# bilancia_smart_no_route.net
KiCad netlist of a schematic drawn in EAGLE
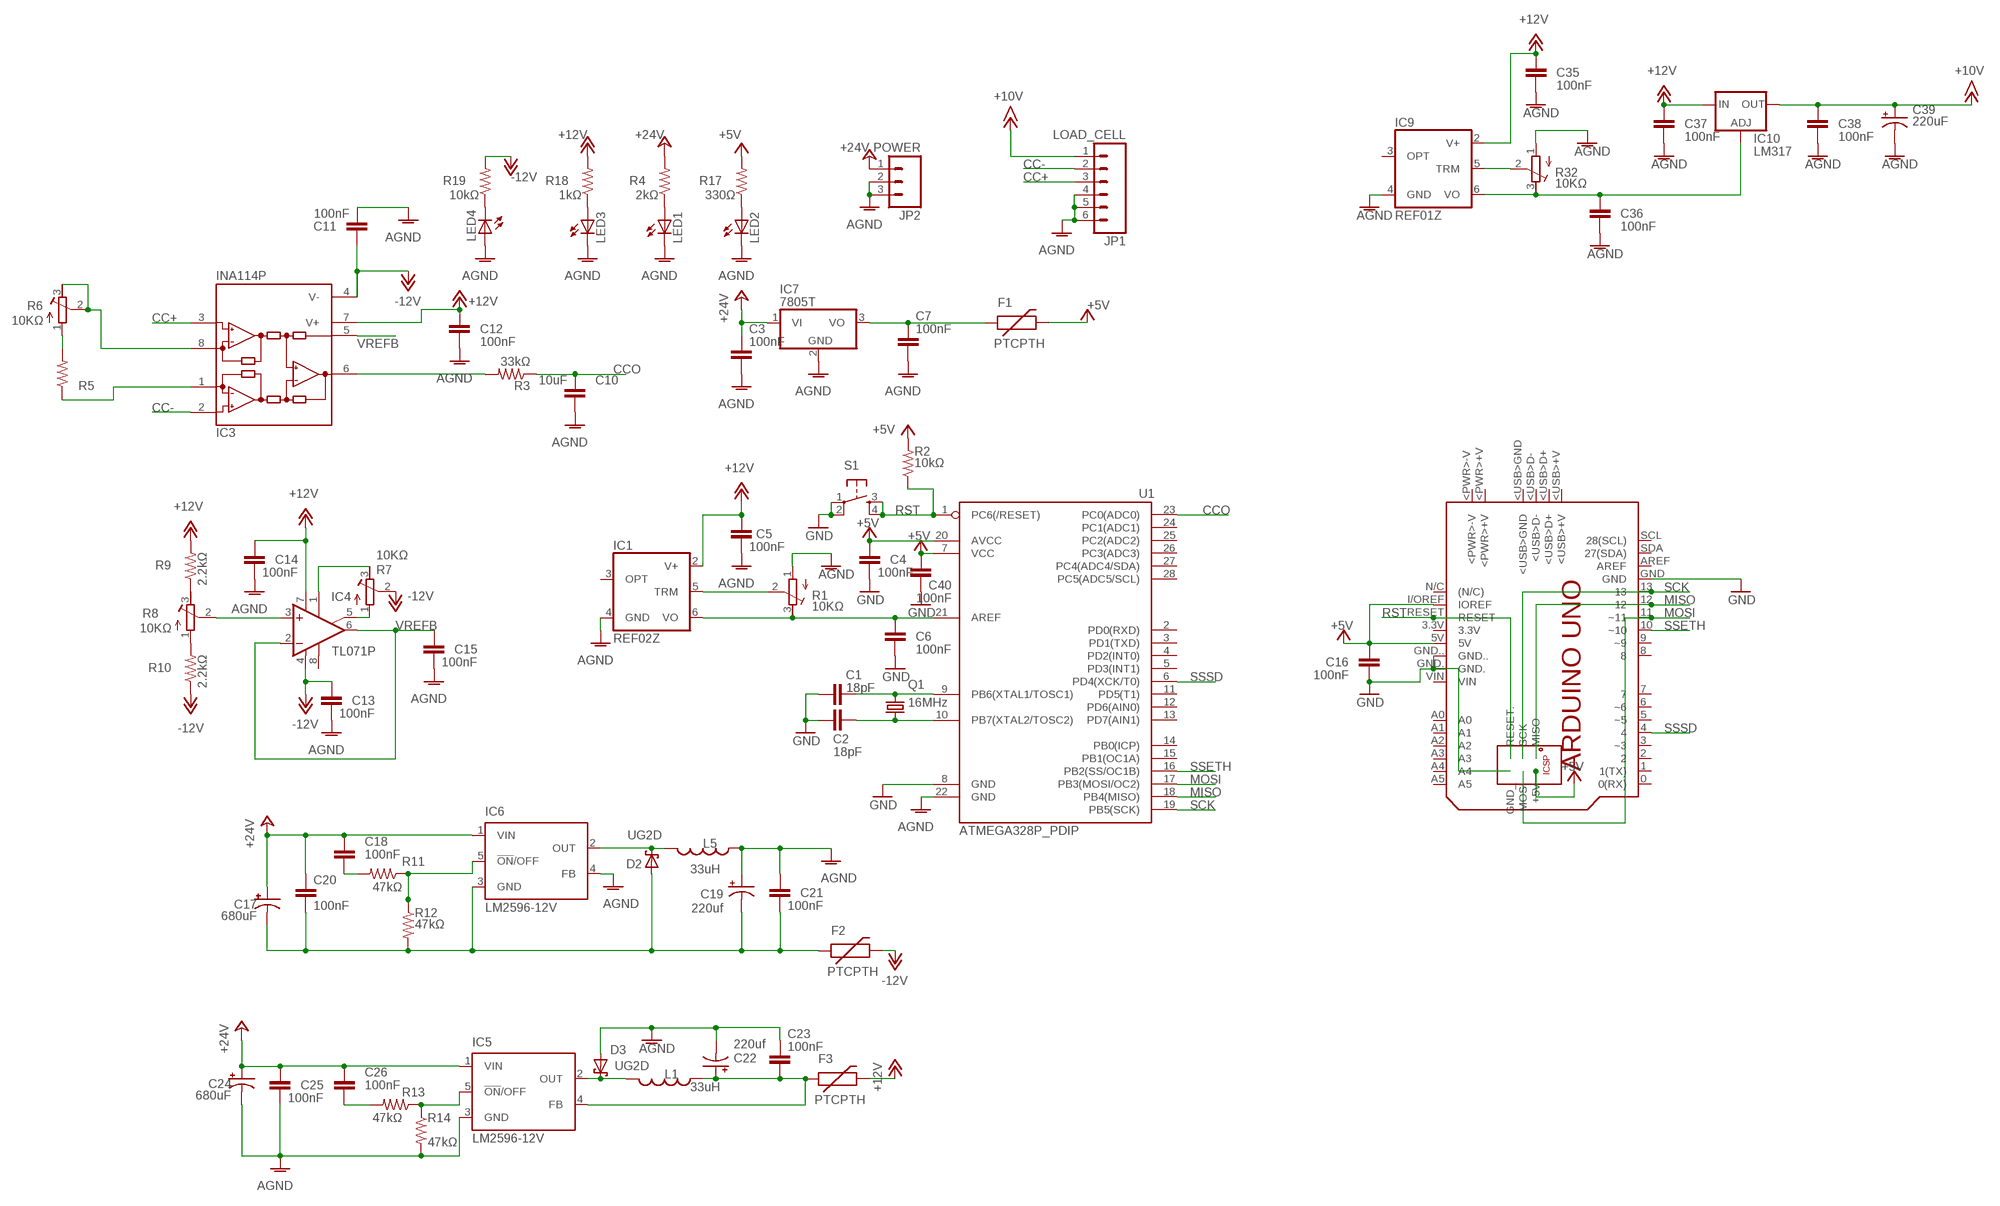
[diagram p0: schematic, sheet 1]

(export (version "E")
  (design (tool "Eeschema 10.0.6"))
  (components
    (comp (ref "C1")
      (value "18pF")
      (footprint "eagle-import:C2.5-2")
      (libsource (lib "eagle-import") (part "C2.5/2"))
    )
    (comp (ref "C2")
      (value "18pF")
      (footprint "eagle-import:C2.5-2")
      (libsource (lib "eagle-import") (part "C2.5/2"))
    )
    (comp (ref "C3")
      (value "100nF")
      (footprint "eagle-import:C2.5-2")
      (libsource (lib "eagle-import") (part "C2.5/2"))
    )
    (comp (ref "C4")
      (value "100nF")
      (footprint "eagle-import:C2.5-2")
      (libsource (lib "eagle-import") (part "C2.5/2"))
    )
    (comp (ref "C5")
      (value "100nF")
      (footprint "eagle-import:C2.5-2")
      (libsource (lib "eagle-import") (part "C2.5/2"))
    )
    (comp (ref "C6")
      (value "100nF")
      (footprint "eagle-import:C2.5-2")
      (libsource (lib "eagle-import") (part "C2.5/2"))
    )
    (comp (ref "C7")
      (value "100nF")
      (footprint "eagle-import:C2.5-2")
      (libsource (lib "eagle-import") (part "C2.5/2"))
    )
    (comp (ref "C10")
      (value "10uF")
      (footprint "eagle-import:C2.5-2")
      (libsource (lib "eagle-import") (part "C2.5/2"))
    )
    (comp (ref "C11")
      (value "100nF")
      (footprint "eagle-import:C2.5-2")
      (libsource (lib "eagle-import") (part "C2.5/2"))
    )
    (comp (ref "C12")
      (value "100nF")
      (footprint "eagle-import:C2.5-2")
      (libsource (lib "eagle-import") (part "C2.5/2"))
    )
    (comp (ref "C13")
      (value "100nF")
      (footprint "eagle-import:C2.5-2")
      (libsource (lib "eagle-import") (part "C2.5/2"))
    )
    (comp (ref "C14")
      (value "100nF")
      (footprint "eagle-import:C2.5-2")
      (libsource (lib "eagle-import") (part "C2.5/2"))
    )
    (comp (ref "C15")
      (value "100nF")
      (footprint "eagle-import:C2.5-2")
      (libsource (lib "eagle-import") (part "C2.5/2"))
    )
    (comp (ref "C16")
      (value "100nF")
      (footprint "eagle-import:C2.5-2")
      (libsource (lib "eagle-import") (part "C2.5/2"))
    )
    (comp (ref "C17")
      (value "680uF")
      (footprint "eagle-import:E5-8,5")
      (libsource (lib "eagle-import") (part "CPOL-USE5-8.5"))
    )
    (comp (ref "C18")
      (value "100nF")
      (footprint "eagle-import:C2.5-2")
      (libsource (lib "eagle-import") (part "C2.5/2"))
    )
    (comp (ref "C19")
      (value "220uf")
      (footprint "eagle-import:E5-8,5")
      (libsource (lib "eagle-import") (part "CPOL-USE5-8.5"))
    )
    (comp (ref "C20")
      (value "100nF")
      (footprint "eagle-import:C2.5-2")
      (libsource (lib "eagle-import") (part "C2.5/2"))
    )
    (comp (ref "C21")
      (value "100nF")
      (footprint "eagle-import:C2.5-2")
      (libsource (lib "eagle-import") (part "C2.5/2"))
    )
    (comp (ref "C22")
      (value "220uf")
      (footprint "eagle-import:E5-8,5")
      (libsource (lib "eagle-import") (part "CPOL-USE5-8.5"))
    )
    (comp (ref "C23")
      (value "100nF")
      (footprint "eagle-import:C2.5-2")
      (libsource (lib "eagle-import") (part "C2.5/2"))
    )
    (comp (ref "C24")
      (value "680uF")
      (footprint "eagle-import:E5-8,5")
      (libsource (lib "eagle-import") (part "CPOL-USE5-8.5"))
    )
    (comp (ref "C25")
      (value "100nF")
      (footprint "eagle-import:C2.5-2")
      (libsource (lib "eagle-import") (part "C2.5/2"))
    )
    (comp (ref "C26")
      (value "100nF")
      (footprint "eagle-import:C2.5-2")
      (libsource (lib "eagle-import") (part "C2.5/2"))
    )
    (comp (ref "C35")
      (value "100nF")
      (footprint "eagle-import:C2.5-2")
      (libsource (lib "eagle-import") (part "C2.5/2"))
    )
    (comp (ref "C36")
      (value "100nF")
      (footprint "eagle-import:C2.5-2")
      (libsource (lib "eagle-import") (part "C2.5/2"))
    )
    (comp (ref "C37")
      (value "100nF")
      (footprint "eagle-import:C2.5-2")
      (libsource (lib "eagle-import") (part "C2.5/2"))
    )
    (comp (ref "C38")
      (value "100nF")
      (footprint "eagle-import:C2.5-2")
      (libsource (lib "eagle-import") (part "C2.5/2"))
    )
    (comp (ref "C39")
      (value "220uF")
      (footprint "eagle-import:CPOL-RADIAL-100UF-25V")
      (libsource (lib "eagle-import") (part "CAP_POLPTH1"))
    )
    (comp (ref "C40")
      (value "100nF")
      (footprint "eagle-import:C2.5-2")
      (libsource (lib "eagle-import") (part "C2.5/2"))
    )
    (comp (ref "D2")
      (value "UG2D")
      (footprint "eagle-import:DO41-7")
      (libsource (lib "eagle-import") (part "SCHOTTKY-DIODEDO41-7"))
    )
    (comp (ref "D3")
      (value "UG2D")
      (footprint "eagle-import:DO41-7")
      (libsource (lib "eagle-import") (part "SCHOTTKY-DIODEDO41-7"))
    )
    (comp (ref "F1")
      (value "PTCPTH")
      (footprint "eagle-import:PTC")
      (libsource (lib "eagle-import") (part "PTCPTH"))
    )
    (comp (ref "F2")
      (value "PTCPTH")
      (footprint "eagle-import:PTC")
      (libsource (lib "eagle-import") (part "PTCPTH"))
    )
    (comp (ref "F3")
      (value "PTCPTH")
      (footprint "eagle-import:PTC")
      (libsource (lib "eagle-import") (part "PTCPTH"))
    )
    (comp (ref "IC1")
      (value "REF02Z")
      (footprint "eagle-import:DIL08")
      (libsource (lib "eagle-import") (part "REF02Z"))
    )
    (comp (ref "IC3")
      (value "INA114P")
      (footprint "eagle-import:DIL08")
      (fields (field (name "MF") "TEXAS INSTRUMENTS") (field (name "MPN") "INA114BP"))
      (libsource (lib "eagle-import") (part "INA114P"))
    )
    (comp (ref "IC4")
      (value "TL071P")
      (footprint "eagle-import:DIL08")
      (libsource (lib "eagle-import") (part "TL071P"))
    )
    (comp (ref "IC5")
      (value "LM2596-12V")
      (footprint "eagle-import:T05D")
      (fields (field (name "MPN") "LM2596T-ADJ/LF02"))
      (libsource (lib "eagle-import") (part "LM2596T"))
    )
    (comp (ref "IC6")
      (value "LM2596-12V")
      (footprint "eagle-import:T05D")
      (fields (field (name "MPN") "LM2596T-ADJ/LF02"))
      (libsource (lib "eagle-import") (part "LM2596T"))
    )
    (comp (ref "IC7")
      (value "7805T")
      (footprint "eagle-import:TO220H")
      (libsource (lib "eagle-import") (part "78T05"))
    )
    (comp (ref "IC9")
      (value "REF01Z")
      (footprint "eagle-import:DIL08")
      (libsource (lib "eagle-import") (part "REF01Z"))
    )
    (comp (ref "IC10")
      (value "LM317")
      (footprint "eagle-import:317TS")
      (libsource (lib "eagle-import") (part "LM317TS"))
    )
    (comp (ref "JP1")
      (value "LOAD_CELL")
      (footprint "eagle-import:1X06")
      (libsource (lib "eagle-import") (part "M06SIP"))
    )
    (comp (ref "JP2")
      (value "POWER")
      (footprint "eagle-import:1X03")
      (libsource (lib "eagle-import") (part "M03PTH"))
    )
    (comp (ref "L1")
      (value "33uH")
      (footprint "eagle-import:RLB0912")
      (libsource (lib "eagle-import") (part "INDUCTORRLB0912"))
    )
    (comp (ref "L5")
      (value "33uH")
      (footprint "eagle-import:RLB0912")
      (libsource (lib "eagle-import") (part "INDUCTORRLB0912"))
    )
    (comp (ref "LED1")
      (value "MINIMIDI_LED5MM")
      (footprint "eagle-import:MINIMIDI_LED5MM")
      (libsource (lib "eagle-import") (part "MINIMIDI_LED5MM"))
    )
    (comp (ref "LED2")
      (value "MINIMIDI_LED5MM")
      (footprint "eagle-import:MINIMIDI_LED5MM")
      (libsource (lib "eagle-import") (part "MINIMIDI_LED5MM"))
    )
    (comp (ref "LED3")
      (value "MINIMIDI_LED5MM")
      (footprint "eagle-import:MINIMIDI_LED5MM")
      (libsource (lib "eagle-import") (part "MINIMIDI_LED5MM"))
    )
    (comp (ref "LED4")
      (value "MINIMIDI_LED5MM")
      (footprint "eagle-import:MINIMIDI_LED5MM")
      (libsource (lib "eagle-import") (part "MINIMIDI_LED5MM"))
    )
    (comp (ref "PCB1")
      (value "ARDUINO_UNO")
      (footprint "eagle-import:ARDUINO_UNO")
      (libsource (lib "eagle-import") (part "ARDUINO_UNO"))
    )
    (comp (ref "Q1")
      (value "16MHz")
      (footprint "eagle-import:HC49_S")
      (libsource (lib "eagle-import") (part "CRYSTALHC49S"))
    )
    (comp (ref "R1")
      (value "10KΩ")
      (footprint "eagle-import:RTRIM64W")
      (libsource (lib "eagle-import") (part "R-TRIMM64W"))
    )
    (comp (ref "R2")
      (value "10kΩ")
      (footprint "eagle-import:0207_10")
      (libsource (lib "eagle-import") (part "R-US_0207/10"))
    )
    (comp (ref "R3")
      (value "33kΩ")
      (footprint "eagle-import:0207_10")
      (libsource (lib "eagle-import") (part "R-US_0207/10"))
    )
    (comp (ref "R4")
      (value "2kΩ")
      (footprint "eagle-import:0207_10")
      (libsource (lib "eagle-import") (part "R-US_0207/10"))
    )
    (comp (ref "R5")
      (value "R-US_0207/10")
      (footprint "eagle-import:0207_10")
      (libsource (lib "eagle-import") (part "R-US_0207/10"))
    )
    (comp (ref "R6")
      (value "10KΩ")
      (footprint "eagle-import:RTRIM64W")
      (libsource (lib "eagle-import") (part "R-TRIMM64W"))
    )
    (comp (ref "R7")
      (value "10KΩ")
      (footprint "eagle-import:RTRIM64W")
      (libsource (lib "eagle-import") (part "R-TRIMM64W"))
    )
    (comp (ref "R8")
      (value "10KΩ")
      (footprint "eagle-import:RTRIM64W")
      (libsource (lib "eagle-import") (part "R-TRIMM64W"))
    )
    (comp (ref "R9")
      (value "2.2kΩ")
      (footprint "eagle-import:0207_10")
      (libsource (lib "eagle-import") (part "R-US_0207/10"))
    )
    (comp (ref "R10")
      (value "2.2kΩ")
      (footprint "eagle-import:0207_10")
      (libsource (lib "eagle-import") (part "R-US_0207/10"))
    )
    (comp (ref "R11")
      (value "47kΩ")
      (footprint "eagle-import:0207_2V")
      (libsource (lib "eagle-import") (part "R-US_0207/2V"))
    )
    (comp (ref "R12")
      (value "47kΩ")
      (footprint "eagle-import:0207_2V")
      (libsource (lib "eagle-import") (part "R-US_0207/2V"))
    )
    (comp (ref "R13")
      (value "47kΩ")
      (footprint "eagle-import:0207_2V")
      (libsource (lib "eagle-import") (part "R-US_0207/2V"))
    )
    (comp (ref "R14")
      (value "47kΩ")
      (footprint "eagle-import:0207_2V")
      (libsource (lib "eagle-import") (part "R-US_0207/2V"))
    )
    (comp (ref "R17")
      (value "330Ω")
      (footprint "eagle-import:0207_10")
      (libsource (lib "eagle-import") (part "R-US_0207/10"))
    )
    (comp (ref "R18")
      (value "1kΩ")
      (footprint "eagle-import:0207_10")
      (libsource (lib "eagle-import") (part "R-US_0207/10"))
    )
    (comp (ref "R19")
      (value "10kΩ")
      (footprint "eagle-import:0207_10")
      (libsource (lib "eagle-import") (part "R-US_0207/10"))
    )
    (comp (ref "R32")
      (value "10KΩ")
      (footprint "eagle-import:RTRIM64W")
      (libsource (lib "eagle-import") (part "R-TRIMM64W"))
    )
    (comp (ref "S1")
      (value "TAC_SWITCHPTH")
      (footprint "eagle-import:TACTILE-PTH")
      (libsource (lib "eagle-import") (part "TAC_SWITCHPTH"))
    )
    (comp (ref "U1")
      (value "ATMEGA328P_PDIP")
      (footprint "eagle-import:DIL28-3")
      (libsource (lib "eagle-import") (part "ATMEGA328P_PDIP"))
    )
  )
  (nets
    (net (code "1") (name "+5V") (class "Default")
      (node (ref "C16") (pin "2") (pinfunction "2_2") (pintype "passive"))
      (node (ref "C4") (pin "2") (pinfunction "2_2") (pintype "passive"))
      (node (ref "C40") (pin "2") (pinfunction "2_2") (pintype "passive"))
      (node (ref "F1") (pin "P$2") (pinfunction "2_P$2") (pintype "bidirectional"))
      (node (ref "PCB1") (pin "+5V") (pinfunction "+5V_+5V") (pintype "bidirectional"))
      (node (ref "PCB1") (pin "5V") (pinfunction "5V_5V") (pintype "bidirectional"))
      (node (ref "PCB1") (pin "I/OREF") (pinfunction "IOREF_I/OREF") (pintype "bidirectional"))
      (node (ref "R17") (pin "2") (pinfunction "2_2") (pintype "passive"))
      (node (ref "R2") (pin "2") (pinfunction "2_2") (pintype "passive"))
      (node (ref "U1") (pin "20") (pinfunction "AVCC_20") (pintype "bidirectional"))
      (node (ref "U1") (pin "7") (pinfunction "VCC_7") (pintype "bidirectional"))
    )
    (net (code "2") (name "+10V") (class "Default")
      (node (ref "C38") (pin "2") (pinfunction "2_2") (pintype "passive"))
      (node (ref "C39") (pin "1") (pinfunction "+_1") (pintype "passive"))
      (node (ref "IC10") (pin "2") (pinfunction "OUT_2") (pintype "passive"))
      (node (ref "JP1") (pin "1") (pinfunction "1_1") (pintype "passive"))
    )
    (net (code "3") (name "+12V") (class "Default")
      (node (ref "C12") (pin "2") (pinfunction "2_2") (pintype "passive"))
      (node (ref "C14") (pin "2") (pinfunction "2_2") (pintype "passive"))
      (node (ref "C35") (pin "2") (pinfunction "2_2") (pintype "passive"))
      (node (ref "C37") (pin "2") (pinfunction "2_2") (pintype "passive"))
      (node (ref "C5") (pin "1") (pinfunction "1_1") (pintype "passive"))
      (node (ref "F3") (pin "P$2") (pinfunction "2_P$2") (pintype "bidirectional"))
      (node (ref "IC1") (pin "2") (pinfunction "V+_2") (pintype "power_in"))
      (node (ref "IC10") (pin "3") (pinfunction "IN_3") (pintype "input"))
      (node (ref "IC3") (pin "7") (pinfunction "V+_7") (pintype "power_in"))
      (node (ref "IC4") (pin "7") (pinfunction "V+_7") (pintype "power_in"))
      (node (ref "IC9") (pin "2") (pinfunction "V+_2") (pintype "power_in"))
      (node (ref "R18") (pin "2") (pinfunction "2_2") (pintype "passive"))
      (node (ref "R9") (pin "2") (pinfunction "2_2") (pintype "passive"))
    )
    (net (code "4") (name "+24V") (class "Default")
      (node (ref "C17") (pin "+") (pinfunction "+_+") (pintype "passive"))
      (node (ref "C18") (pin "1") (pinfunction "1_1") (pintype "passive"))
      (node (ref "C20") (pin "1") (pinfunction "1_1") (pintype "passive"))
      (node (ref "C24") (pin "+") (pinfunction "+_+") (pintype "passive"))
      (node (ref "C25") (pin "1") (pinfunction "1_1") (pintype "passive"))
      (node (ref "C26") (pin "1") (pinfunction "1_1") (pintype "passive"))
      (node (ref "C3") (pin "2") (pinfunction "2_2") (pintype "passive"))
      (node (ref "IC5") (pin "1") (pinfunction "VIN_1") (pintype "input"))
      (node (ref "IC6") (pin "1") (pinfunction "VIN_1") (pintype "input"))
      (node (ref "IC7") (pin "1") (pinfunction "VI_1") (pintype "input"))
      (node (ref "JP2") (pin "1") (pinfunction "1_1") (pintype "passive"))
      (node (ref "R4") (pin "2") (pinfunction "2_2") (pintype "passive"))
    )
    (net (code "5") (name "-12V") (class "Default")
      (node (ref "C11") (pin "2") (pinfunction "2_2") (pintype "passive"))
      (node (ref "C13") (pin "2") (pinfunction "2_2") (pintype "passive"))
      (node (ref "F2") (pin "P$2") (pinfunction "2_P$2") (pintype "bidirectional"))
      (node (ref "IC3") (pin "4") (pinfunction "V-_4") (pintype "power_in"))
      (node (ref "IC4") (pin "4") (pinfunction "V-_4") (pintype "power_in"))
      (node (ref "R10") (pin "1") (pinfunction "1_1") (pintype "passive"))
      (node (ref "R19") (pin "2") (pinfunction "2_2") (pintype "passive"))
      (node (ref "R7") (pin "2") (pinfunction "S_2") (pintype "passive"))
    )
    (net (code "6") (name "/CC+") (class "Default")
      (node (ref "IC3") (pin "3") (pinfunction "+IN_3") (pintype "input"))
      (node (ref "JP1") (pin "3") (pinfunction "3_3") (pintype "passive"))
    )
    (net (code "7") (name "/CC-") (class "Default")
      (node (ref "IC3") (pin "2") (pinfunction "-IN_2") (pintype "input"))
      (node (ref "JP1") (pin "2") (pinfunction "2_2") (pintype "passive"))
    )
    (net (code "8") (name "/CCO") (class "Default")
      (node (ref "C10") (pin "2") (pinfunction "2_2") (pintype "passive"))
      (node (ref "R3") (pin "1") (pinfunction "1_1") (pintype "passive"))
      (node (ref "U1") (pin "23") (pinfunction "PC0(ADC0)_23") (pintype "bidirectional"))
    )
    (net (code "9") (name "/MISO") (class "Default")
      (node (ref "PCB1") (pin "12") (pinfunction "12_12") (pintype "bidirectional"))
      (node (ref "PCB1") (pin "MISO") (pinfunction "MISO_MISO") (pintype "bidirectional"))
      (node (ref "U1") (pin "18") (pinfunction "PB4(MISO)_18") (pintype "bidirectional"))
    )
    (net (code "10") (name "/MOSI") (class "Default")
      (node (ref "PCB1") (pin "11") (pinfunction "~{11}_11") (pintype "bidirectional"))
      (node (ref "PCB1") (pin "MOSI") (pinfunction "MOSI_MOSI") (pintype "bidirectional"))
      (node (ref "U1") (pin "17") (pinfunction "PB3(MOSI/OC2)_17") (pintype "bidirectional"))
    )
    (net (code "11") (name "/RST") (class "Default")
      (node (ref "PCB1") (pin "RESET") (pinfunction "RESET_RESET") (pintype "bidirectional"))
      (node (ref "PCB1") (pin "RESET.") (pinfunction "RESET._RESET.") (pintype "bidirectional"))
      (node (ref "R2") (pin "1") (pinfunction "1_1") (pintype "passive"))
      (node (ref "S1") (pin "3") (pinfunction "3_3") (pintype "passive"))
      (node (ref "S1") (pin "4") (pinfunction "4_4") (pintype "passive"))
      (node (ref "U1") (pin "1") (pinfunction "PC6(/RESET)_1") (pintype "bidirectional"))
    )
    (net (code "12") (name "/SCK") (class "Default")
      (node (ref "PCB1") (pin "13") (pinfunction "13_13") (pintype "bidirectional"))
      (node (ref "PCB1") (pin "SCK") (pinfunction "SCK_SCK") (pintype "bidirectional"))
      (node (ref "U1") (pin "19") (pinfunction "PB5(SCK)_19") (pintype "bidirectional"))
    )
    (net (code "13") (name "/SSETH") (class "Default")
      (node (ref "PCB1") (pin "10") (pinfunction "~{10}_10") (pintype "bidirectional"))
      (node (ref "U1") (pin "16") (pinfunction "PB2(SS/OC1B)_16") (pintype "bidirectional"))
    )
    (net (code "14") (name "/SSSD") (class "Default")
      (node (ref "PCB1") (pin "4") (pinfunction "4_4") (pintype "bidirectional"))
      (node (ref "U1") (pin "6") (pinfunction "PD4(XCK/T0)_6") (pintype "bidirectional"))
    )
    (net (code "15") (name "/VREFB") (class "Default")
      (node (ref "C15") (pin "2") (pinfunction "2_2") (pintype "passive"))
      (node (ref "IC3") (pin "5") (pinfunction "REF_5") (pintype "passive"))
      (node (ref "IC4") (pin "2") (pinfunction "-IN_2") (pintype "input"))
      (node (ref "IC4") (pin "6") (pinfunction "OUT_6") (pintype "output"))
    )
    (net (code "16") (name "AGND") (class "Default")
      (node (ref "C10") (pin "1") (pinfunction "1_1") (pintype "passive"))
      (node (ref "C11") (pin "1") (pinfunction "1_1") (pintype "passive"))
      (node (ref "C12") (pin "1") (pinfunction "1_1") (pintype "passive"))
      (node (ref "C13") (pin "1") (pinfunction "1_1") (pintype "passive"))
      (node (ref "C14") (pin "1") (pinfunction "1_1") (pintype "passive"))
      (node (ref "C15") (pin "1") (pinfunction "1_1") (pintype "passive"))
      (node (ref "C19") (pin "+") (pinfunction "+_+") (pintype "passive"))
      (node (ref "C21") (pin "1") (pinfunction "1_1") (pintype "passive"))
      (node (ref "C22") (pin "-") (pinfunction "-_-") (pintype "passive"))
      (node (ref "C23") (pin "2") (pinfunction "2_2") (pintype "passive"))
      (node (ref "C24") (pin "-") (pinfunction "-_-") (pintype "passive"))
      (node (ref "C25") (pin "2") (pinfunction "2_2") (pintype "passive"))
      (node (ref "C3") (pin "1") (pinfunction "1_1") (pintype "passive"))
      (node (ref "C35") (pin "1") (pinfunction "1_1") (pintype "passive"))
      (node (ref "C36") (pin "1") (pinfunction "1_1") (pintype "passive"))
      (node (ref "C37") (pin "1") (pinfunction "1_1") (pintype "passive"))
      (node (ref "C38") (pin "1") (pinfunction "1_1") (pintype "passive"))
      (node (ref "C39") (pin "2") (pinfunction "-_2") (pintype "passive"))
      (node (ref "C5") (pin "2") (pinfunction "2_2") (pintype "passive"))
      (node (ref "C7") (pin "1") (pinfunction "1_1") (pintype "passive"))
      (node (ref "D3") (pin "A") (pinfunction "A_A") (pintype "passive"))
      (node (ref "IC1") (pin "4") (pinfunction "GND_4") (pintype "power_in"))
      (node (ref "IC5") (pin "3") (pinfunction "GND_3") (pintype "power_in"))
      (node (ref "IC6") (pin "4") (pinfunction "FB_4") (pintype "input"))
      (node (ref "IC7") (pin "2") (pinfunction "GND_2") (pintype "passive"))
      (node (ref "IC9") (pin "4") (pinfunction "GND_4") (pintype "power_in"))
      (node (ref "JP1") (pin "4") (pinfunction "4_4") (pintype "passive"))
      (node (ref "JP1") (pin "5") (pinfunction "5_5") (pintype "passive"))
      (node (ref "JP1") (pin "6") (pinfunction "6_6") (pintype "passive"))
      (node (ref "JP2") (pin "2") (pinfunction "2_2") (pintype "passive"))
      (node (ref "JP2") (pin "3") (pinfunction "3_3") (pintype "passive"))
      (node (ref "L5") (pin "1") (pinfunction "1_1") (pintype "passive"))
      (node (ref "LED1") (pin "K") (pinfunction "C_K") (pintype "passive"))
      (node (ref "LED2") (pin "K") (pinfunction "C_K") (pintype "passive"))
      (node (ref "LED3") (pin "K") (pinfunction "C_K") (pintype "passive"))
      (node (ref "LED4") (pin "A") (pinfunction "A_A") (pintype "passive"))
      (node (ref "R1") (pin "1") (pinfunction "E_1") (pintype "passive"))
      (node (ref "R14") (pin "2") (pinfunction "2_2") (pintype "passive"))
      (node (ref "R32") (pin "1") (pinfunction "E_1") (pintype "passive"))
      (node (ref "U1") (pin "22") (pinfunction "GND_22") (pintype "bidirectional"))
    )
    (net (code "17") (name "GND") (class "Default")
      (node (ref "C1") (pin "1") (pinfunction "1_1") (pintype "passive"))
      (node (ref "C16") (pin "1") (pinfunction "1_1") (pintype "passive"))
      (node (ref "C2") (pin "1") (pinfunction "1_1") (pintype "passive"))
      (node (ref "C4") (pin "1") (pinfunction "1_1") (pintype "passive"))
      (node (ref "C40") (pin "1") (pinfunction "1_1") (pintype "passive"))
      (node (ref "C6") (pin "1") (pinfunction "1_1") (pintype "passive"))
      (node (ref "PCB1") (pin "GND") (pinfunction "GND_GND") (pintype "bidirectional"))
      (node (ref "PCB1") (pin "GND.") (pinfunction "GND._GND.") (pintype "bidirectional"))
      (node (ref "PCB1") (pin "GND..") (pinfunction "GND.._GND..") (pintype "bidirectional"))
      (node (ref "PCB1") (pin "GND_") (pinfunction "GND__GND_") (pintype "bidirectional"))
      (node (ref "S1") (pin "1") (pinfunction "1_1") (pintype "passive"))
      (node (ref "S1") (pin "2") (pinfunction "2_2") (pintype "passive"))
      (node (ref "U1") (pin "8") (pinfunction "GND_8") (pintype "bidirectional"))
    )
    (net (code "18") (name "Net-(C18-Pad2)") (class "Default")
      (node (ref "C18") (pin "2") (pinfunction "2_2") (pintype "passive"))
      (node (ref "R11") (pin "2") (pinfunction "2_2") (pintype "passive"))
    )
    (net (code "19") (name "Net-(C26-Pad2)") (class "Default")
      (node (ref "C26") (pin "2") (pinfunction "2_2") (pintype "passive"))
      (node (ref "R13") (pin "2") (pinfunction "2_2") (pintype "passive"))
    )
    (net (code "20") (name "Net-(F1-1)") (class "Default")
      (node (ref "C7") (pin "2") (pinfunction "2_2") (pintype "passive"))
      (node (ref "F1") (pin "P$1") (pinfunction "1_P$1") (pintype "bidirectional"))
      (node (ref "IC7") (pin "3") (pinfunction "VO_3") (pintype "passive"))
    )
    (net (code "21") (name "Net-(F2-1)") (class "Default")
      (node (ref "C17") (pin "-") (pinfunction "-_-") (pintype "passive"))
      (node (ref "C19") (pin "-") (pinfunction "-_-") (pintype "passive"))
      (node (ref "C20") (pin "2") (pinfunction "2_2") (pintype "passive"))
      (node (ref "C21") (pin "2") (pinfunction "2_2") (pintype "passive"))
      (node (ref "D2") (pin "A") (pinfunction "A_A") (pintype "passive"))
      (node (ref "F2") (pin "P$1") (pinfunction "1_P$1") (pintype "bidirectional"))
      (node (ref "IC6") (pin "3") (pinfunction "GND_3") (pintype "power_in"))
      (node (ref "R12") (pin "2") (pinfunction "2_2") (pintype "passive"))
    )
    (net (code "22") (name "Net-(F3-1)") (class "Default")
      (node (ref "C22") (pin "+") (pinfunction "+_+") (pintype "passive"))
      (node (ref "C23") (pin "1") (pinfunction "1_1") (pintype "passive"))
      (node (ref "F3") (pin "P$1") (pinfunction "1_P$1") (pintype "bidirectional"))
      (node (ref "IC5") (pin "4") (pinfunction "FB_4") (pintype "input"))
      (node (ref "L1") (pin "1") (pinfunction "1_1") (pintype "passive"))
    )
    (net (code "23") (name "Net-(IC1-TRM)") (class "Default")
      (node (ref "IC1") (pin "5") (pinfunction "TRM_5") (pintype "input"))
      (node (ref "R1") (pin "2") (pinfunction "S_2") (pintype "passive"))
    )
    (net (code "24") (name "Net-(IC1-VO)") (class "Default")
      (node (ref "C6") (pin "2") (pinfunction "2_2") (pintype "passive"))
      (node (ref "IC1") (pin "6") (pinfunction "VO_6") (pintype "output"))
      (node (ref "R1") (pin "3") (pinfunction "A_3") (pintype "passive"))
      (node (ref "U1") (pin "21") (pinfunction "AREF_21") (pintype "bidirectional"))
    )
    (net (code "25") (name "Net-(IC3-OUT)") (class "Default")
      (node (ref "IC3") (pin "6") (pinfunction "OUT_6") (pintype "output"))
      (node (ref "R3") (pin "2") (pinfunction "2_2") (pintype "passive"))
    )
    (net (code "26") (name "Net-(IC3-RG-Pad1)") (class "Default")
      (node (ref "IC3") (pin "1") (pinfunction "RG_1") (pintype "passive"))
      (node (ref "R5") (pin "1") (pinfunction "1_1") (pintype "passive"))
    )
    (net (code "27") (name "Net-(IC4-+IN)") (class "Default")
      (node (ref "IC4") (pin "3") (pinfunction "+IN_3") (pintype "input"))
      (node (ref "R8") (pin "2") (pinfunction "S_2") (pintype "passive"))
    )
    (net (code "28") (name "Net-(IC4-ON1)") (class "Default")
      (node (ref "IC4") (pin "1") (pinfunction "ON1_1") (pintype "passive"))
      (node (ref "R7") (pin "3") (pinfunction "A_3") (pintype "passive"))
    )
    (net (code "29") (name "Net-(IC4-ON2)") (class "Default")
      (node (ref "IC4") (pin "5") (pinfunction "ON2_5") (pintype "passive"))
      (node (ref "R7") (pin "1") (pinfunction "E_1") (pintype "passive"))
    )
    (net (code "30") (name "Net-(IC5-OUT)") (class "Default")
      (node (ref "D3") (pin "C") (pinfunction "C_C") (pintype "passive"))
      (node (ref "IC5") (pin "2") (pinfunction "OUT_2") (pintype "output"))
      (node (ref "L1") (pin "2") (pinfunction "2_2") (pintype "passive"))
    )
    (net (code "31") (name "Net-(IC5-~{ON}{slash}OFF)") (class "Default")
      (node (ref "IC5") (pin "5") (pinfunction "~{ON}/OFF_5") (pintype "input"))
      (node (ref "R13") (pin "1") (pinfunction "1_1") (pintype "passive"))
      (node (ref "R14") (pin "1") (pinfunction "1_1") (pintype "passive"))
    )
    (net (code "32") (name "Net-(IC6-OUT)") (class "Default")
      (node (ref "D2") (pin "C") (pinfunction "C_C") (pintype "passive"))
      (node (ref "IC6") (pin "2") (pinfunction "OUT_2") (pintype "output"))
      (node (ref "L5") (pin "2") (pinfunction "2_2") (pintype "passive"))
    )
    (net (code "33") (name "Net-(IC6-~{ON}{slash}OFF)") (class "Default")
      (node (ref "IC6") (pin "5") (pinfunction "~{ON}/OFF_5") (pintype "input"))
      (node (ref "R11") (pin "1") (pinfunction "1_1") (pintype "passive"))
      (node (ref "R12") (pin "1") (pinfunction "1_1") (pintype "passive"))
    )
    (net (code "34") (name "Net-(IC9-TRM)") (class "Default")
      (node (ref "IC9") (pin "5") (pinfunction "TRM_5") (pintype "input"))
      (node (ref "R32") (pin "2") (pinfunction "S_2") (pintype "passive"))
    )
    (net (code "35") (name "Net-(IC10-ADJ)") (class "Default")
      (node (ref "C36") (pin "2") (pinfunction "2_2") (pintype "passive"))
      (node (ref "IC10") (pin "1") (pinfunction "ADJ_1") (pintype "input"))
      (node (ref "IC9") (pin "6") (pinfunction "VO_6") (pintype "output"))
      (node (ref "R32") (pin "3") (pinfunction "A_3") (pintype "passive"))
    )
    (net (code "36") (name "Net-(LED1-PadA)") (class "Default")
      (node (ref "LED1") (pin "A") (pinfunction "A_A") (pintype "passive"))
      (node (ref "R4") (pin "1") (pinfunction "1_1") (pintype "passive"))
    )
    (net (code "37") (name "Net-(LED2-PadA)") (class "Default")
      (node (ref "LED2") (pin "A") (pinfunction "A_A") (pintype "passive"))
      (node (ref "R17") (pin "1") (pinfunction "1_1") (pintype "passive"))
    )
    (net (code "38") (name "Net-(LED3-PadA)") (class "Default")
      (node (ref "LED3") (pin "A") (pinfunction "A_A") (pintype "passive"))
      (node (ref "R18") (pin "1") (pinfunction "1_1") (pintype "passive"))
    )
    (net (code "39") (name "Net-(LED4-C)") (class "Default")
      (node (ref "LED4") (pin "K") (pinfunction "C_K") (pintype "passive"))
      (node (ref "R19") (pin "1") (pinfunction "1_1") (pintype "passive"))
    )
    (net (code "40") (name "Net-(R6-A)") (class "Default")
      (node (ref "IC3") (pin "8") (pinfunction "RG_8") (pintype "passive"))
      (node (ref "R6") (pin "2") (pinfunction "S_2") (pintype "passive"))
      (node (ref "R6") (pin "3") (pinfunction "A_3") (pintype "passive"))
    )
    (net (code "41") (name "Net-(R6-E)") (class "Default")
      (node (ref "R5") (pin "2") (pinfunction "2_2") (pintype "passive"))
      (node (ref "R6") (pin "1") (pinfunction "E_1") (pintype "passive"))
    )
    (net (code "42") (name "Net-(R8-A)") (class "Default")
      (node (ref "R8") (pin "3") (pinfunction "A_3") (pintype "passive"))
      (node (ref "R9") (pin "1") (pinfunction "1_1") (pintype "passive"))
    )
    (net (code "43") (name "Net-(R8-E)") (class "Default")
      (node (ref "R10") (pin "2") (pinfunction "2_2") (pintype "passive"))
      (node (ref "R8") (pin "1") (pinfunction "E_1") (pintype "passive"))
    )
    (net (code "44") (name "Net-(U1-PB6(XTAL1{slash}TOSC1))") (class "Default")
      (node (ref "C1") (pin "2") (pinfunction "2_2") (pintype "passive"))
      (node (ref "Q1") (pin "1") (pinfunction "1_1") (pintype "passive"))
      (node (ref "U1") (pin "9") (pinfunction "PB6(XTAL1/TOSC1)_9") (pintype "bidirectional"))
    )
    (net (code "45") (name "Net-(U1-PB7(XTAL2{slash}TOSC2))") (class "Default")
      (node (ref "C2") (pin "2") (pinfunction "2_2") (pintype "passive"))
      (node (ref "Q1") (pin "2") (pinfunction "2_2") (pintype "passive"))
      (node (ref "U1") (pin "10") (pinfunction "PB7(XTAL2/TOSC2)_10") (pintype "bidirectional"))
    )
    (net (code "46") (name "unconnected-(IC1-OPT-Pad3)") (class "Default")
      (node (ref "IC1") (pin "3") (pinfunction "OPT_3") (pintype "output"))
    )
    (net (code "47") (name "unconnected-(IC4-OPT-Pad8)") (class "Default")
      (node (ref "IC4") (pin "8") (pinfunction "OPT_8") (pintype "passive"))
    )
    (net (code "48") (name "unconnected-(IC9-OPT-Pad3)") (class "Default")
      (node (ref "IC9") (pin "3") (pinfunction "OPT_3") (pintype "output"))
    )
    (net (code "49") (name "unconnected-(PCB1-(N{slash}C)-PadN{slash}C)") (class "Default")
      (node (ref "PCB1") (pin "N/C") (pinfunction "(N/C)_N/C") (pintype "bidirectional"))
    )
    (net (code "50") (name "unconnected-(PCB1-0(RX)-Pad0)") (class "Default")
      (node (ref "PCB1") (pin "0") (pinfunction "0(RX)_0") (pintype "bidirectional"))
    )
    (net (code "51") (name "unconnected-(PCB1-1(TX)-Pad1)") (class "Default")
      (node (ref "PCB1") (pin "1") (pinfunction "1(TX)_1") (pintype "bidirectional"))
    )
    (net (code "52") (name "unconnected-(PCB1-27(SDA)-PadSDA)") (class "Default")
      (node (ref "PCB1") (pin "SDA") (pinfunction "27(SDA)_SDA") (pintype "bidirectional"))
    )
    (net (code "53") (name "unconnected-(PCB1-28(SCL)-PadSCL)") (class "Default")
      (node (ref "PCB1") (pin "SCL") (pinfunction "28(SCL)_SCL") (pintype "bidirectional"))
    )
    (net (code "54") (name "unconnected-(PCB1-Pad2)") (class "Default")
      (node (ref "PCB1") (pin "2") (pinfunction "2_2") (pintype "bidirectional"))
    )
    (net (code "55") (name "unconnected-(PCB1-Pad3.3V)") (class "Default")
      (node (ref "PCB1") (pin "3.3V") (pinfunction "3.3V_3.3V") (pintype "bidirectional"))
    )
    (net (code "56") (name "unconnected-(PCB1-Pad7)") (class "Default")
      (node (ref "PCB1") (pin "7") (pinfunction "7_7") (pintype "bidirectional"))
    )
    (net (code "57") (name "unconnected-(PCB1-Pad8)") (class "Default")
      (node (ref "PCB1") (pin "8") (pinfunction "8_8") (pintype "bidirectional"))
    )
    (net (code "58") (name "unconnected-(PCB1-Pad<PWR>+V)") (class "Default")
      (node (ref "PCB1") (pin "<PWR>+V") (pinfunction "<PWR>+V_<PWR>+V") (pintype "bidirectional"))
    )
    (net (code "59") (name "unconnected-(PCB1-Pad<PWR>-V)") (class "Default")
      (node (ref "PCB1") (pin "<PWR>-V") (pinfunction "<PWR>-V_<PWR>-V") (pintype "bidirectional"))
    )
    (net (code "60") (name "unconnected-(PCB1-Pad<USB>+V)") (class "Default")
      (node (ref "PCB1") (pin "<USB>+V") (pinfunction "<USB>+V_<USB>+V") (pintype "bidirectional"))
    )
    (net (code "61") (name "unconnected-(PCB1-Pad<USB>D+)") (class "Default")
      (node (ref "PCB1") (pin "<USB>D+") (pinfunction "<USB>D+_<USB>D+") (pintype "bidirectional"))
    )
    (net (code "62") (name "unconnected-(PCB1-Pad<USB>D-)") (class "Default")
      (node (ref "PCB1") (pin "<USB>D-") (pinfunction "<USB>D-_<USB>D-") (pintype "bidirectional"))
    )
    (net (code "63") (name "unconnected-(PCB1-Pad<USB>GND)") (class "Default")
      (node (ref "PCB1") (pin "<USB>GND") (pinfunction "<USB>GND_<USB>GND") (pintype "bidirectional"))
    )
    (net (code "64") (name "unconnected-(PCB1-PadA0)") (class "Default")
      (node (ref "PCB1") (pin "A0") (pinfunction "A0_A0") (pintype "bidirectional"))
    )
    (net (code "65") (name "unconnected-(PCB1-PadA1)") (class "Default")
      (node (ref "PCB1") (pin "A1") (pinfunction "A1_A1") (pintype "bidirectional"))
    )
    (net (code "66") (name "unconnected-(PCB1-PadA2)") (class "Default")
      (node (ref "PCB1") (pin "A2") (pinfunction "A2_A2") (pintype "bidirectional"))
    )
    (net (code "67") (name "unconnected-(PCB1-PadA3)") (class "Default")
      (node (ref "PCB1") (pin "A3") (pinfunction "A3_A3") (pintype "bidirectional"))
    )
    (net (code "68") (name "unconnected-(PCB1-PadA4)") (class "Default")
      (node (ref "PCB1") (pin "A4") (pinfunction "A4_A4") (pintype "bidirectional"))
    )
    (net (code "69") (name "unconnected-(PCB1-PadA5)") (class "Default")
      (node (ref "PCB1") (pin "A5") (pinfunction "A5_A5") (pintype "bidirectional"))
    )
    (net (code "70") (name "unconnected-(PCB1-PadAREF)") (class "Default")
      (node (ref "PCB1") (pin "AREF") (pinfunction "AREF_AREF") (pintype "bidirectional"))
    )
    (net (code "71") (name "unconnected-(PCB1-PadVIN)") (class "Default")
      (node (ref "PCB1") (pin "VIN") (pinfunction "VIN_VIN") (pintype "bidirectional"))
    )
    (net (code "72") (name "unconnected-(PCB1-~{3}-Pad3)") (class "Default")
      (node (ref "PCB1") (pin "3") (pinfunction "~{3}_3") (pintype "bidirectional"))
    )
    (net (code "73") (name "unconnected-(PCB1-~{5}-Pad5)") (class "Default")
      (node (ref "PCB1") (pin "5") (pinfunction "~{5}_5") (pintype "bidirectional"))
    )
    (net (code "74") (name "unconnected-(PCB1-~{6}-Pad6)") (class "Default")
      (node (ref "PCB1") (pin "6") (pinfunction "~{6}_6") (pintype "bidirectional"))
    )
    (net (code "75") (name "unconnected-(PCB1-~{9}-Pad9)") (class "Default")
      (node (ref "PCB1") (pin "9") (pinfunction "~{9}_9") (pintype "bidirectional"))
    )
    (net (code "76") (name "unconnected-(U1-PB0(ICP)-Pad14)") (class "Default")
      (node (ref "U1") (pin "14") (pinfunction "PB0(ICP)_14") (pintype "bidirectional"))
    )
    (net (code "77") (name "unconnected-(U1-PB1(OC1A)-Pad15)") (class "Default")
      (node (ref "U1") (pin "15") (pinfunction "PB1(OC1A)_15") (pintype "bidirectional"))
    )
    (net (code "78") (name "unconnected-(U1-PC1(ADC1)-Pad24)") (class "Default")
      (node (ref "U1") (pin "24") (pinfunction "PC1(ADC1)_24") (pintype "bidirectional"))
    )
    (net (code "79") (name "unconnected-(U1-PC2(ADC2)-Pad25)") (class "Default")
      (node (ref "U1") (pin "25") (pinfunction "PC2(ADC2)_25") (pintype "bidirectional"))
    )
    (net (code "80") (name "unconnected-(U1-PC3(ADC3)-Pad26)") (class "Default")
      (node (ref "U1") (pin "26") (pinfunction "PC3(ADC3)_26") (pintype "bidirectional"))
    )
    (net (code "81") (name "unconnected-(U1-PC4(ADC4{slash}SDA)-Pad27)") (class "Default")
      (node (ref "U1") (pin "27") (pinfunction "PC4(ADC4/SDA)_27") (pintype "bidirectional"))
    )
    (net (code "82") (name "unconnected-(U1-PC5(ADC5{slash}SCL)-Pad28)") (class "Default")
      (node (ref "U1") (pin "28") (pinfunction "PC5(ADC5/SCL)_28") (pintype "bidirectional"))
    )
    (net (code "83") (name "unconnected-(U1-PD0(RXD)-Pad2)") (class "Default")
      (node (ref "U1") (pin "2") (pinfunction "PD0(RXD)_2") (pintype "bidirectional"))
    )
    (net (code "84") (name "unconnected-(U1-PD1(TXD)-Pad3)") (class "Default")
      (node (ref "U1") (pin "3") (pinfunction "PD1(TXD)_3") (pintype "bidirectional"))
    )
    (net (code "85") (name "unconnected-(U1-PD2(INT0)-Pad4)") (class "Default")
      (node (ref "U1") (pin "4") (pinfunction "PD2(INT0)_4") (pintype "bidirectional"))
    )
    (net (code "86") (name "unconnected-(U1-PD3(INT1)-Pad5)") (class "Default")
      (node (ref "U1") (pin "5") (pinfunction "PD3(INT1)_5") (pintype "bidirectional"))
    )
    (net (code "87") (name "unconnected-(U1-PD5(T1)-Pad11)") (class "Default")
      (node (ref "U1") (pin "11") (pinfunction "PD5(T1)_11") (pintype "bidirectional"))
    )
    (net (code "88") (name "unconnected-(U1-PD6(AIN0)-Pad12)") (class "Default")
      (node (ref "U1") (pin "12") (pinfunction "PD6(AIN0)_12") (pintype "bidirectional"))
    )
    (net (code "89") (name "unconnected-(U1-PD7(AIN1)-Pad13)") (class "Default")
      (node (ref "U1") (pin "13") (pinfunction "PD7(AIN1)_13") (pintype "bidirectional"))
    )
  )
)
